# ATTiny10DevBrd.net
KiCad netlist of a schematic drawn in EAGLE
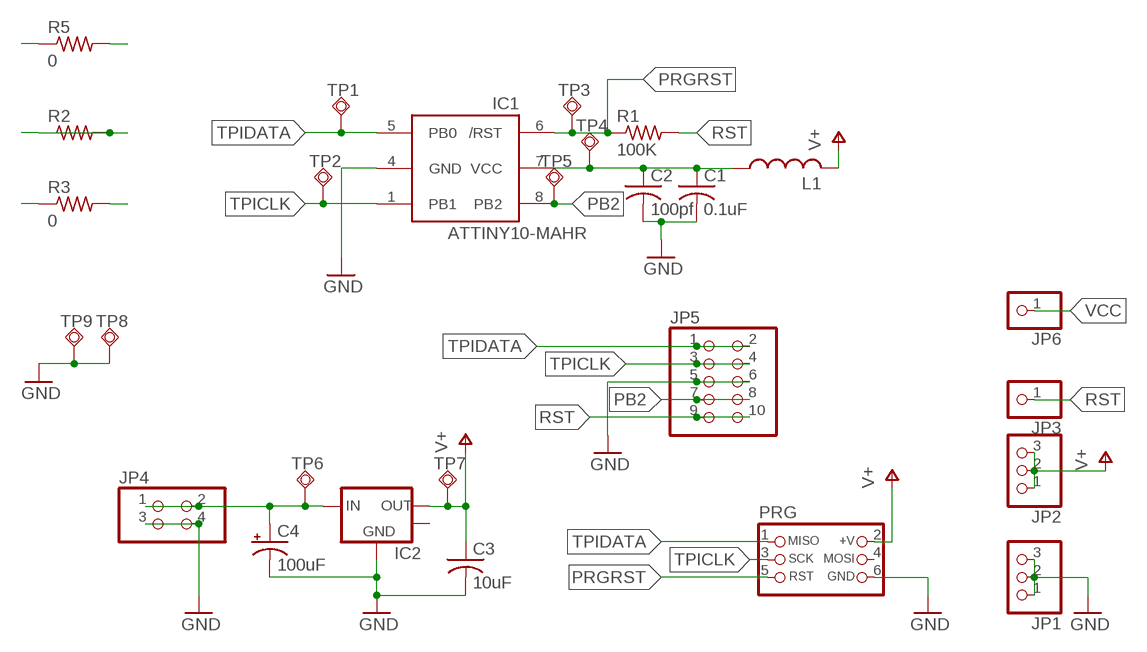
[diagram p0: schematic, sheet 1]

(export (version "E")
  (design (tool "Eeschema 10.0.6"))
  (components
    (comp (ref "C1")
      (value "0.1uF")
      (footprint "eagle-import:C0603")
      (libsource (lib "eagle-import") (part "adafruit_C-USC0603"))
    )
    (comp (ref "C2")
      (value "100pf")
      (footprint "eagle-import:C0402")
      (libsource (lib "eagle-import") (part "adafruit_C-USC0402"))
    )
    (comp (ref "C3")
      (value "10uF")
      (footprint "eagle-import:C0805K")
      (libsource (lib "eagle-import") (part "C-USC0805K"))
    )
    (comp (ref "C4")
      (value "100uF")
      (footprint "eagle-import:PANASONIC_E")
      (libsource (lib "eagle-import") (part "CPOL-USE"))
    )
    (comp (ref "IC1")
      (value "ATTINY10-MAHR")
      (footprint "eagle-import:UDFN-8")
      (libsource (lib "eagle-import") (part "ATTINY10-MAHR"))
    )
    (comp (ref "IC2")
      (value "V_REG_LM1117SOT223")
      (footprint "eagle-import:SOT223")
      (libsource (lib "eagle-import") (part "V_REG_LM1117SOT223"))
    )
    (comp (ref "JP1")
      (value "PINHD-1X3")
      (footprint "eagle-import:1X03")
      (libsource (lib "eagle-import") (part "PINHD-1X3"))
    )
    (comp (ref "JP2")
      (value "PINHD-1X3")
      (footprint "eagle-import:1X03")
      (libsource (lib "eagle-import") (part "PINHD-1X3"))
    )
    (comp (ref "JP3")
      (value "PINHD-1X1")
      (footprint "eagle-import:1X01")
      (libsource (lib "eagle-import") (part "PINHD-1X1"))
    )
    (comp (ref "JP4")
      (value "PINHD-2X2")
      (footprint "eagle-import:2X02")
      (libsource (lib "eagle-import") (part "PINHD-2X2"))
    )
    (comp (ref "JP5")
      (value "PINHD-2X5")
      (footprint "eagle-import:2X05")
      (libsource (lib "eagle-import") (part "PINHD-2X5"))
    )
    (comp (ref "JP6")
      (value "PINHD-1X1")
      (footprint "eagle-import:1X01")
      (libsource (lib "eagle-import") (part "PINHD-1X1"))
    )
    (comp (ref "L1")
      (value "L-USL1812")
      (footprint "eagle-import:L1812")
      (libsource (lib "eagle-import") (part "L-USL1812"))
    )
    (comp (ref "PRG")
      (value "CON_HEADER_PRG_AVR_ICSP_ETCH")
      (footprint "eagle-import:HEADER_PRG_2X03_ETCH")
      (libsource (lib "eagle-import") (part "CON_HEADER_PRG_AVR_ICSP_ETCH"))
    )
    (comp (ref "R1")
      (value "100K")
      (footprint "eagle-import:R0805")
      (libsource (lib "eagle-import") (part "R-US_R0805"))
    )
    (comp (ref "R2")
      (value "R-US_M1206")
      (footprint "eagle-import:M1206")
      (libsource (lib "eagle-import") (part "R-US_M1206"))
    )
    (comp (ref "R3")
      (value "0")
      (footprint "eagle-import:M1206")
      (libsource (lib "eagle-import") (part "R-US_M1206"))
    )
    (comp (ref "R5")
      (value "0")
      (footprint "eagle-import:R0805")
      (libsource (lib "eagle-import") (part "R-US_R0805"))
    )
    (comp (ref "TP1")
      (value "TPSQTP12R")
      (footprint "eagle-import:TP12R")
      (libsource (lib "eagle-import") (part "TPSQTP12R"))
    )
    (comp (ref "TP2")
      (value "TPSQTP12R")
      (footprint "eagle-import:TP12R")
      (libsource (lib "eagle-import") (part "TPSQTP12R"))
    )
    (comp (ref "TP3")
      (value "TPSQTP12R")
      (footprint "eagle-import:TP12R")
      (libsource (lib "eagle-import") (part "TPSQTP12R"))
    )
    (comp (ref "TP4")
      (value "TPSQTP12R")
      (footprint "eagle-import:TP12R")
      (libsource (lib "eagle-import") (part "TPSQTP12R"))
    )
    (comp (ref "TP5")
      (value "TPSQTP12R")
      (footprint "eagle-import:TP12R")
      (libsource (lib "eagle-import") (part "TPSQTP12R"))
    )
    (comp (ref "TP6")
      (value "TPSQTP12R")
      (footprint "eagle-import:TP12R")
      (libsource (lib "eagle-import") (part "TPSQTP12R"))
    )
    (comp (ref "TP7")
      (value "TPSQTP12R")
      (footprint "eagle-import:TP12R")
      (libsource (lib "eagle-import") (part "TPSQTP12R"))
    )
    (comp (ref "TP8")
      (value "TPSQTP12R")
      (footprint "eagle-import:TP12R")
      (libsource (lib "eagle-import") (part "TPSQTP12R"))
    )
    (comp (ref "TP9")
      (value "TPSQTP12R")
      (footprint "eagle-import:TP12R")
      (libsource (lib "eagle-import") (part "TPSQTP12R"))
    )
  )
  (nets
    (net (code "1") (name "/OUT") (class "Default")
      (node (ref "IC2") (pin "4") (pinfunction "OUT_4") (pintype "power_in"))
    )
    (net (code "2") (name "GND") (class "Default")
      (node (ref "C1") (pin "2") (pinfunction "2_2") (pintype "passive"))
      (node (ref "C2") (pin "2") (pinfunction "2_2") (pintype "passive"))
      (node (ref "C3") (pin "2") (pinfunction "2_2") (pintype "passive"))
      (node (ref "C4") (pin "-") (pinfunction "-_-") (pintype "passive"))
      (node (ref "IC1") (pin "4") (pinfunction "GND_4") (pintype "power_in"))
      (node (ref "IC2") (pin "1") (pinfunction "GND_1") (pintype "input"))
      (node (ref "JP1") (pin "1") (pinfunction "1_1") (pintype "passive"))
      (node (ref "JP1") (pin "2") (pinfunction "2_2") (pintype "passive"))
      (node (ref "JP1") (pin "3") (pinfunction "3_3") (pintype "passive"))
      (node (ref "JP4") (pin "3") (pinfunction "3_3") (pintype "passive"))
      (node (ref "JP4") (pin "4") (pinfunction "4_4") (pintype "passive"))
      (node (ref "JP5") (pin "5") (pinfunction "5_5") (pintype "passive"))
      (node (ref "JP5") (pin "6") (pinfunction "6_6") (pintype "passive"))
      (node (ref "PRG") (pin "6") (pinfunction "GND_6") (pintype "passive"))
      (node (ref "TP8") (pin "TP") (pinfunction "TP_TP") (pintype "input"))
      (node (ref "TP9") (pin "TP") (pinfunction "TP_TP") (pintype "input"))
    )
    (net (code "3") (name "Net-(IC2-IN)") (class "Default")
      (node (ref "C4") (pin "+") (pinfunction "+_+") (pintype "passive"))
      (node (ref "IC2") (pin "3") (pinfunction "IN_3") (pintype "input"))
      (node (ref "JP4") (pin "1") (pinfunction "1_1") (pintype "passive"))
      (node (ref "JP4") (pin "2") (pinfunction "2_2") (pintype "passive"))
      (node (ref "TP6") (pin "TP") (pinfunction "TP_TP") (pintype "input"))
    )
    (net (code "4") (name "PB2") (class "Default")
      (node (ref "IC1") (pin "8") (pinfunction "PB2_8") (pintype "bidirectional"))
      (node (ref "JP5") (pin "7") (pinfunction "7_7") (pintype "passive"))
      (node (ref "JP5") (pin "8") (pinfunction "8_8") (pintype "passive"))
      (node (ref "R3") (pin "1") (pinfunction "1_1") (pintype "passive"))
      (node (ref "R3") (pin "2") (pinfunction "2_2") (pintype "passive"))
      (node (ref "TP5") (pin "TP") (pinfunction "TP_TP") (pintype "input"))
    )
    (net (code "5") (name "PRGRST") (class "Default")
      (node (ref "IC1") (pin "6") (pinfunction "/RST_6") (pintype "bidirectional"))
      (node (ref "PRG") (pin "5") (pinfunction "RST_5") (pintype "passive"))
      (node (ref "R1") (pin "1") (pinfunction "1_1") (pintype "passive"))
      (node (ref "TP3") (pin "TP") (pinfunction "TP_TP") (pintype "input"))
    )
    (net (code "6") (name "RST") (class "Default")
      (node (ref "JP3") (pin "1") (pinfunction "1_1") (pintype "passive"))
      (node (ref "JP5") (pin "10") (pinfunction "10_10") (pintype "passive"))
      (node (ref "JP5") (pin "9") (pinfunction "9_9") (pintype "passive"))
      (node (ref "R1") (pin "2") (pinfunction "2_2") (pintype "passive"))
    )
    (net (code "7") (name "TPICLK") (class "Default")
      (node (ref "IC1") (pin "1") (pinfunction "PB1_1") (pintype "bidirectional"))
      (node (ref "JP5") (pin "3") (pinfunction "3_3") (pintype "passive"))
      (node (ref "JP5") (pin "4") (pinfunction "4_4") (pintype "passive"))
      (node (ref "PRG") (pin "3") (pinfunction "SCK_3") (pintype "passive"))
      (node (ref "R2") (pin "1") (pinfunction "1_1") (pintype "passive"))
      (node (ref "R2") (pin "2") (pinfunction "2_2") (pintype "passive"))
      (node (ref "TP2") (pin "TP") (pinfunction "TP_TP") (pintype "input"))
    )
    (net (code "8") (name "TPIDATA") (class "Default")
      (node (ref "IC1") (pin "5") (pinfunction "PB0_5") (pintype "bidirectional"))
      (node (ref "JP5") (pin "1") (pinfunction "1_1") (pintype "passive"))
      (node (ref "JP5") (pin "2") (pinfunction "2_2") (pintype "passive"))
      (node (ref "PRG") (pin "1") (pinfunction "MISO_1") (pintype "passive"))
      (node (ref "R5") (pin "1") (pinfunction "1_1") (pintype "passive"))
      (node (ref "R5") (pin "2") (pinfunction "2_2") (pintype "passive"))
      (node (ref "TP1") (pin "TP") (pinfunction "TP_TP") (pintype "input"))
    )
    (net (code "9") (name "V+") (class "Default")
      (node (ref "C3") (pin "1") (pinfunction "1_1") (pintype "passive"))
      (node (ref "IC2") (pin "2") (pinfunction "VR-OUTSM_2") (pintype "power_in"))
      (node (ref "JP2") (pin "1") (pinfunction "1_1") (pintype "passive"))
      (node (ref "JP2") (pin "2") (pinfunction "2_2") (pintype "passive"))
      (node (ref "JP2") (pin "3") (pinfunction "3_3") (pintype "passive"))
      (node (ref "L1") (pin "2") (pinfunction "2_2") (pintype "passive"))
      (node (ref "PRG") (pin "2") (pinfunction "+V_2") (pintype "passive"))
      (node (ref "TP7") (pin "TP") (pinfunction "TP_TP") (pintype "input"))
    )
    (net (code "10") (name "VCC") (class "Default")
      (node (ref "C1") (pin "1") (pinfunction "1_1") (pintype "passive"))
      (node (ref "C2") (pin "1") (pinfunction "1_1") (pintype "passive"))
      (node (ref "IC1") (pin "7") (pinfunction "VCC_7") (pintype "power_in"))
      (node (ref "JP6") (pin "1") (pinfunction "1_1") (pintype "passive"))
      (node (ref "L1") (pin "1") (pinfunction "1_1") (pintype "passive"))
      (node (ref "TP4") (pin "TP") (pinfunction "TP_TP") (pintype "input"))
    )
    (net (code "11") (name "unconnected-(PRG-MOSI-Pad4)") (class "Default")
      (node (ref "PRG") (pin "4") (pinfunction "MOSI_4") (pintype "passive"))
    )
  )
)
